# routev11_2.net
KiCad netlist of a schematic drawn in EAGLE
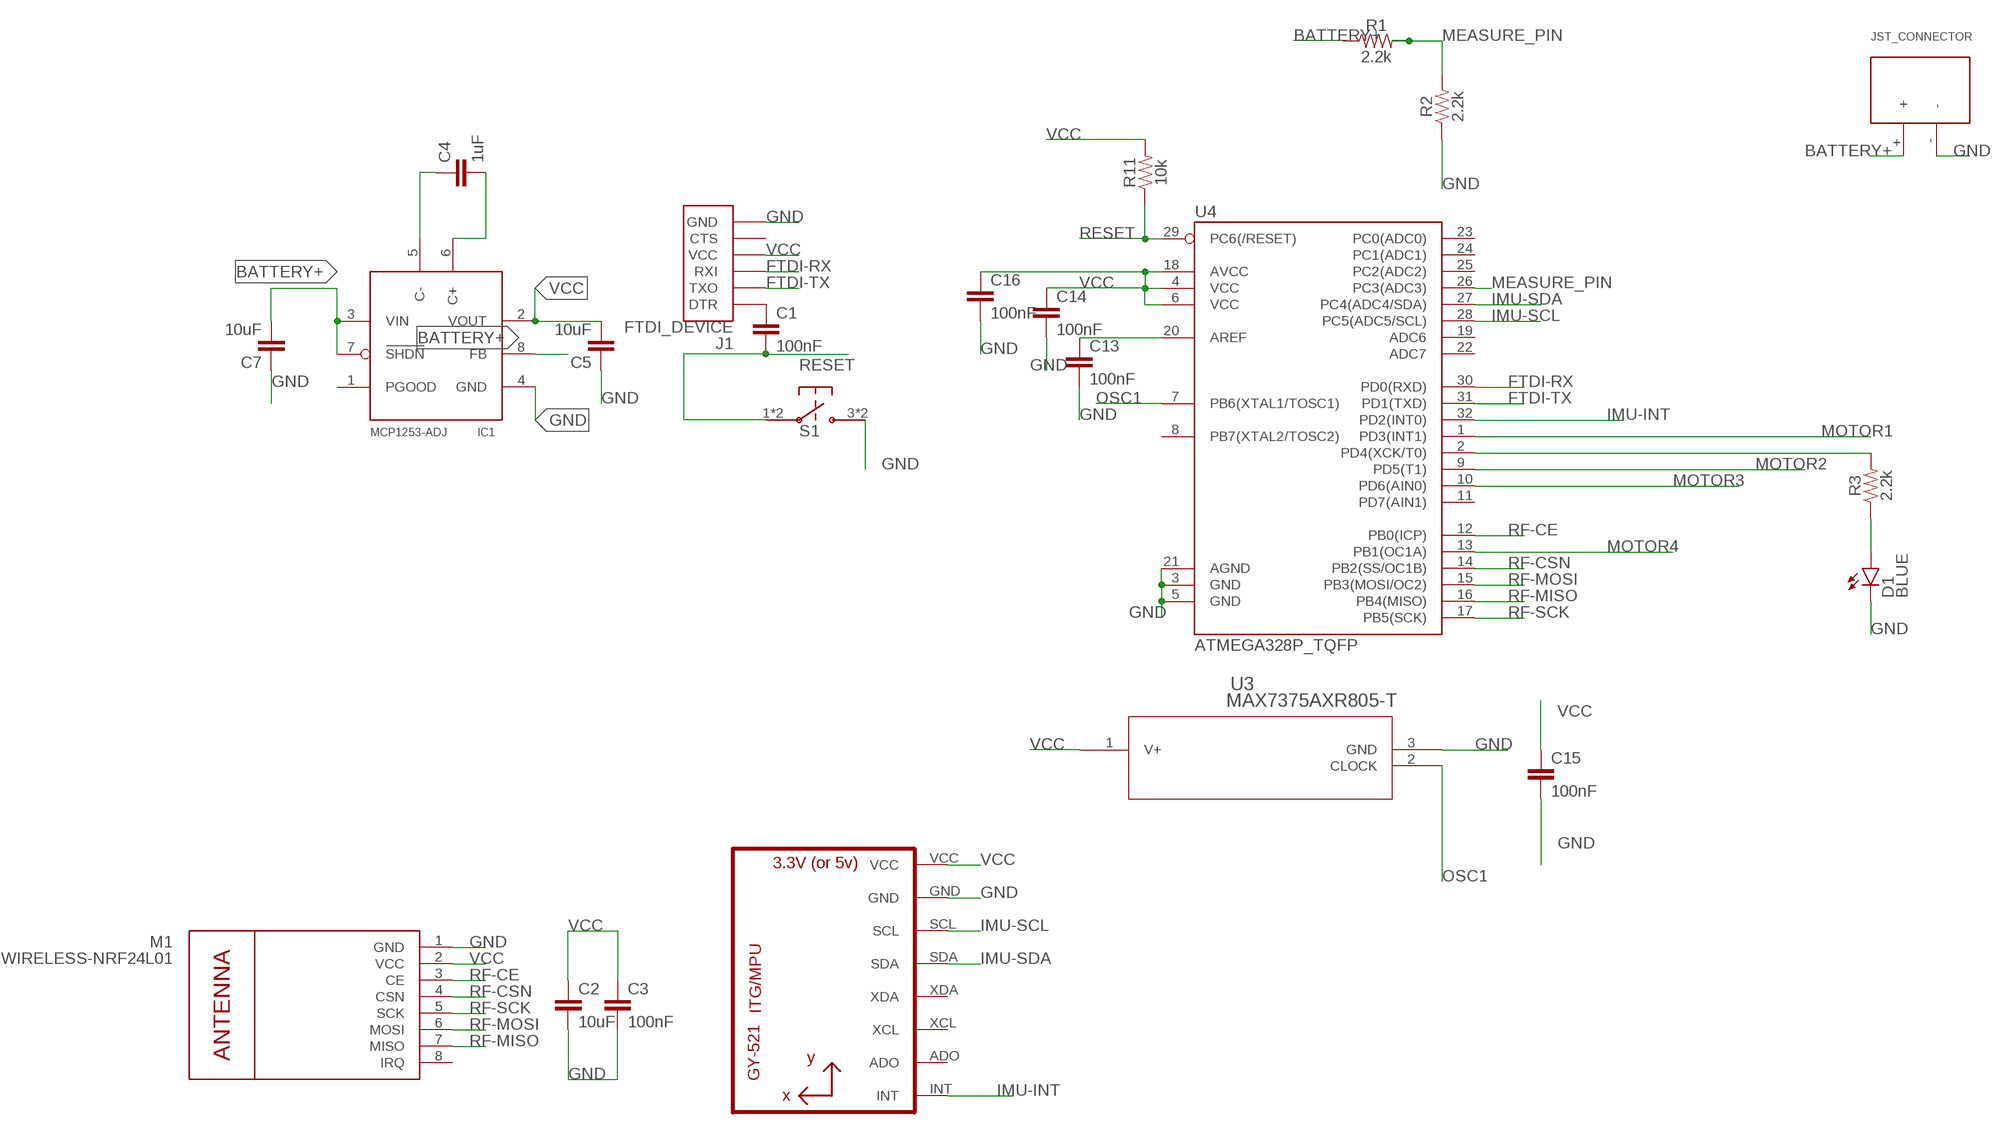
[diagram p0: schematic, sheet 1, part 1 of 2]
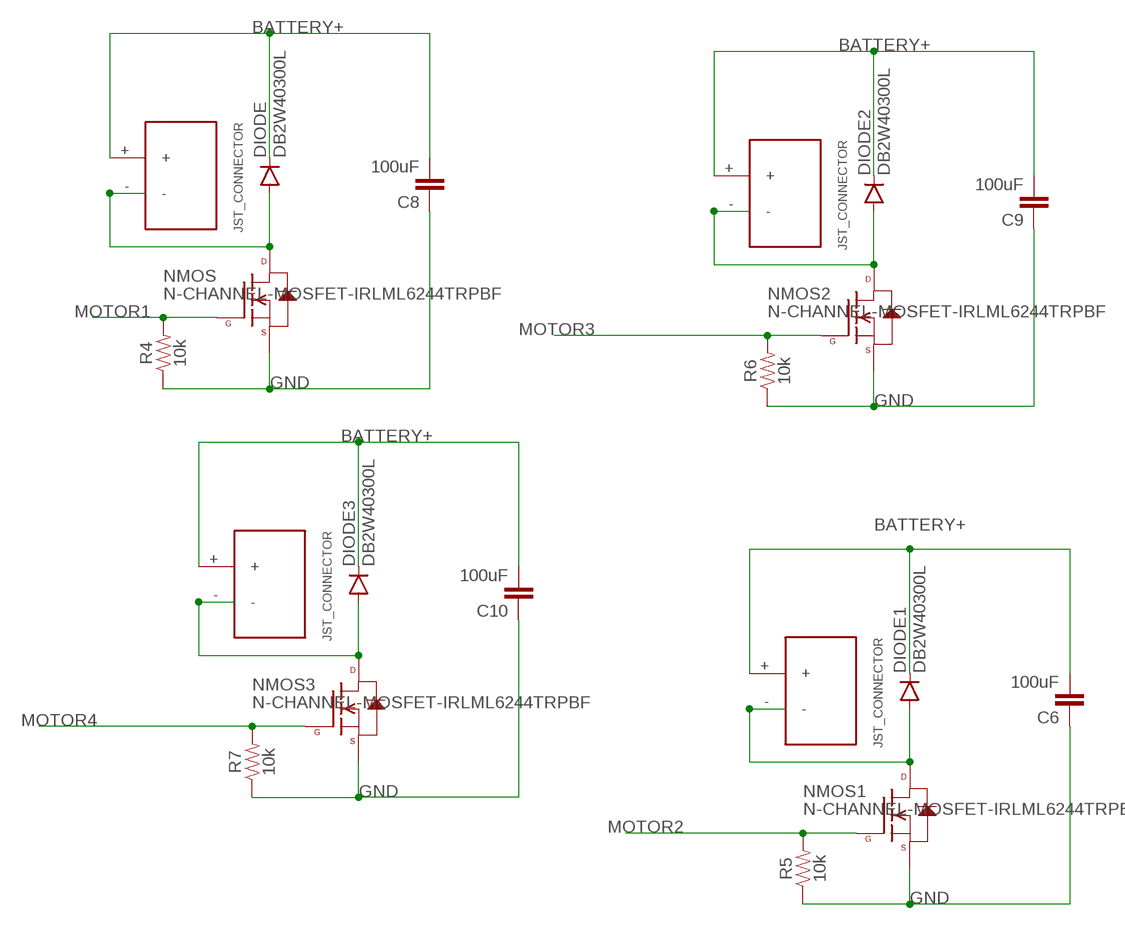
[diagram p1: schematic, sheet 1, part 2 of 2]

(export (version "E")
  (design (tool "Eeschema 10.0.6"))
  (components
    (comp (ref "C1")
      (value "100nF")
      (footprint "eagle-import:0603-CAP")
      (libsource (lib "eagle-import") (part "0.1UF-25V(+80/-20%)(0603)"))
    )
    (comp (ref "C2")
      (value "10uF")
      (footprint "eagle-import:0603-CAP")
      (libsource (lib "eagle-import") (part "CAP0603-CAP"))
    )
    (comp (ref "C3")
      (value "100nF")
      (footprint "eagle-import:0603-CAP")
      (libsource (lib "eagle-import") (part "CAP0603-CAP"))
    )
    (comp (ref "C4")
      (value "1uF")
      (footprint "eagle-import:0603-CAP")
      (libsource (lib "eagle-import") (part "0.1UF-25V(+80/-20%)(0603)"))
    )
    (comp (ref "C5")
      (value "10uF")
      (footprint "eagle-import:0603-CAP")
      (libsource (lib "eagle-import") (part "0.1UF-25V(+80/-20%)(0603)"))
    )
    (comp (ref "C6")
      (value "100uF")
      (footprint "eagle-import:1206")
      (libsource (lib "eagle-import") (part "CAP1206"))
    )
    (comp (ref "C7")
      (value "10uF")
      (footprint "eagle-import:0603-CAP")
      (libsource (lib "eagle-import") (part "0.1UF-25V(+80/-20%)(0603)"))
    )
    (comp (ref "C8")
      (value "100uF")
      (footprint "eagle-import:1206")
      (libsource (lib "eagle-import") (part "CAP1206"))
    )
    (comp (ref "C9")
      (value "100uF")
      (footprint "eagle-import:1206")
      (libsource (lib "eagle-import") (part "CAP1206"))
    )
    (comp (ref "C10")
      (value "100uF")
      (footprint "eagle-import:1206")
      (libsource (lib "eagle-import") (part "CAP1206"))
    )
    (comp (ref "C13")
      (value "100nF")
      (footprint "eagle-import:0603-CAP")
      (libsource (lib "eagle-import") (part "CAP0603-CAP"))
    )
    (comp (ref "C14")
      (value "100nF")
      (footprint "eagle-import:0603-CAP")
      (libsource (lib "eagle-import") (part "CAP0603-CAP"))
    )
    (comp (ref "C15")
      (value "100nF")
      (footprint "eagle-import:0603-CAP")
      (libsource (lib "eagle-import") (part "0.1UF-25V(+80/-20%)(0603)"))
    )
    (comp (ref "C16")
      (value "100nF")
      (footprint "eagle-import:0603-CAP")
      (libsource (lib "eagle-import") (part "CAP0603-CAP"))
    )
    (comp (ref "D1")
      (value "BLUE")
      (footprint "eagle-import:LED-0603")
      (fields (field (name "SPICEPREFIX") "D"))
      (libsource (lib "eagle-import") (part "LED-BLUE0603"))
    )
    (comp (ref "DIODE")
      (value "DB2W40300L")
      (footprint "eagle-import:MINI2-F3-B")
      (libsource (lib "eagle-import") (part "DB2W40300L"))
    )
    (comp (ref "DIODE1")
      (value "DB2W40300L")
      (footprint "eagle-import:MINI2-F3-B")
      (libsource (lib "eagle-import") (part "DB2W40300L"))
    )
    (comp (ref "DIODE2")
      (value "DB2W40300L")
      (footprint "eagle-import:MINI2-F3-B")
      (libsource (lib "eagle-import") (part "DB2W40300L"))
    )
    (comp (ref "DIODE3")
      (value "DB2W40300L")
      (footprint "eagle-import:MINI2-F3-B")
      (libsource (lib "eagle-import") (part "DB2W40300L"))
    )
    (comp (ref "IC1")
      (value "MCP1253-ADJ")
      (footprint "eagle-import:MSOP8")
      (libsource (lib "eagle-import") (part "MCP1253-ADJ"))
    )
    (comp (ref "J1")
      (value "FTDI_DEVICE")
      (footprint "eagle-import:FTDI_DEVICE_SIDE")
      (libsource (lib "eagle-import") (part "FTDI_DEVICE"))
    )
    (comp (ref "M1")
      (value "WIRELESS-NRF24L01")
      (footprint "eagle-import:WIRELESS-NRF24L01")
      (libsource (lib "eagle-import") (part "WIRELESS-NRF24L01"))
    )
    (comp (ref "MOTOR1")
      (value "JST_CONNECTOR_FEMALE")
      (footprint "eagle-import:JST_CONNECTOR_FEMALE")
      (libsource (lib "eagle-import") (part "JST_CONNECTOR_FEMALE"))
    )
    (comp (ref "MOTOR2")
      (value "JST_CONNECTOR_FEMALE")
      (footprint "eagle-import:JST_CONNECTOR_FEMALE")
      (libsource (lib "eagle-import") (part "JST_CONNECTOR_FEMALE"))
    )
    (comp (ref "MOTOR3")
      (value "JST_CONNECTOR_FEMALE")
      (footprint "eagle-import:JST_CONNECTOR_FEMALE")
      (libsource (lib "eagle-import") (part "JST_CONNECTOR_FEMALE"))
    )
    (comp (ref "MOTOR4")
      (value "JST_CONNECTOR_FEMALE")
      (footprint "eagle-import:JST_CONNECTOR_FEMALE")
      (libsource (lib "eagle-import") (part "JST_CONNECTOR_FEMALE"))
    )
    (comp (ref "NMOS")
      (value "N-CHANNEL-MOSFET-IRLML6244TRPBF")
      (footprint "eagle-import:SOT23-3")
      (libsource (lib "eagle-import") (part "N-CHANNEL-MOSFET-IRLML6244TRPBF"))
    )
    (comp (ref "NMOS1")
      (value "N-CHANNEL-MOSFET-IRLML6244TRPBF")
      (footprint "eagle-import:SOT23-3")
      (libsource (lib "eagle-import") (part "N-CHANNEL-MOSFET-IRLML6244TRPBF"))
    )
    (comp (ref "NMOS2")
      (value "N-CHANNEL-MOSFET-IRLML6244TRPBF")
      (footprint "eagle-import:SOT23-3")
      (libsource (lib "eagle-import") (part "N-CHANNEL-MOSFET-IRLML6244TRPBF"))
    )
    (comp (ref "NMOS3")
      (value "N-CHANNEL-MOSFET-IRLML6244TRPBF")
      (footprint "eagle-import:SOT23-3")
      (libsource (lib "eagle-import") (part "N-CHANNEL-MOSFET-IRLML6244TRPBF"))
    )
    (comp (ref "R1")
      (value "2.2k")
      (footprint "eagle-import:0603")
      (libsource (lib "eagle-import") (part "2.2KOHM-0603-1/10W-1%"))
    )
    (comp (ref "R2")
      (value "2.2k")
      (footprint "eagle-import:0603")
      (libsource (lib "eagle-import") (part "2.2KOHM-0603-1/10W-1%"))
    )
    (comp (ref "R3")
      (value "2.2k")
      (footprint "eagle-import:0603")
      (fields (field (name "SPICEPREFIX") "R"))
      (libsource (lib "eagle-import") (part "2.2KOHM-0603-1/10W-1%"))
    )
    (comp (ref "R4")
      (value "10k")
      (footprint "eagle-import:0603")
      (libsource (lib "eagle-import") (part "2.2KOHM-0603-1/10W-1%"))
    )
    (comp (ref "R5")
      (value "10k")
      (footprint "eagle-import:0603")
      (libsource (lib "eagle-import") (part "2.2KOHM-0603-1/10W-1%"))
    )
    (comp (ref "R6")
      (value "10k")
      (footprint "eagle-import:0603")
      (libsource (lib "eagle-import") (part "2.2KOHM-0603-1/10W-1%"))
    )
    (comp (ref "R7")
      (value "10k")
      (footprint "eagle-import:0603")
      (libsource (lib "eagle-import") (part "2.2KOHM-0603-1/10W-1%"))
    )
    (comp (ref "R11")
      (value "10k")
      (footprint "eagle-import:0603")
      (libsource (lib "eagle-import") (part "2.2KOHM-0603-1/10W-1%"))
    )
    (comp (ref "S1")
      (value "TL3315NF100Q")
      (footprint "eagle-import:TL3315NF100Q")
      (fields (field (name "DIGI-KEY_PART_NUMBER") "EG4620CT-ND") (field (name "MF") "E-Switch"))
      (libsource (lib "eagle-import") (part "TL3315NF100Q"))
    )
    (comp (ref "U$1")
      (value "JST_CONNECTOR_FEMALE")
      (footprint "eagle-import:JST_CONNECTOR_FEMALE")
      (libsource (lib "eagle-import") (part "JST_CONNECTOR_FEMALE"))
    )
    (comp (ref "U2")
      (value "GY-521MPU6050")
      (footprint "eagle-import:GY-521")
      (libsource (lib "eagle-import") (part "GY-521MPU6050"))
    )
    (comp (ref "U3")
      (value "MAX7375AXR805-T")
      (footprint "eagle-import:21-0075D")
      (fields (field (name "MF") "Maxim Integrated") (field (name "MP") "MAX7375AXR805+T"))
      (libsource (lib "eagle-import") (part "MAX7375AXR805-T"))
    )
    (comp (ref "U4")
      (value "ATMEGA328P_TQFP")
      (footprint "eagle-import:TQFP32-08")
      (libsource (lib "eagle-import") (part "ATMEGA328P_TQFP"))
    )
  )
  (nets
    (net (code "1") (name "BATTERY+") (class "Default")
      (node (ref "C10") (pin "2") (pinfunction "2_2") (pintype "passive"))
      (node (ref "C6") (pin "2") (pinfunction "2_2") (pintype "passive"))
      (node (ref "C7") (pin "2") (pinfunction "2_2") (pintype "passive"))
      (node (ref "C8") (pin "2") (pinfunction "2_2") (pintype "passive"))
      (node (ref "C9") (pin "2") (pinfunction "2_2") (pintype "passive"))
      (node (ref "DIODE") (pin "NEG") (pinfunction "GPIN_NEG") (pintype "passive"))
      (node (ref "DIODE1") (pin "NEG") (pinfunction "GPIN_NEG") (pintype "passive"))
      (node (ref "DIODE2") (pin "NEG") (pinfunction "GPIN_NEG") (pintype "passive"))
      (node (ref "DIODE3") (pin "NEG") (pinfunction "GPIN_NEG") (pintype "passive"))
      (node (ref "IC1") (pin "3") (pinfunction "VIN_3") (pintype "power_in"))
      (node (ref "IC1") (pin "7") (pinfunction "SHDN_7") (pintype "input"))
      (node (ref "IC1") (pin "8") (pinfunction "FB_8") (pintype "input"))
      (node (ref "MOTOR1") (pin "+") (pinfunction "+_+") (pintype "bidirectional"))
      (node (ref "MOTOR2") (pin "+") (pinfunction "+_+") (pintype "bidirectional"))
      (node (ref "MOTOR3") (pin "+") (pinfunction "+_+") (pintype "bidirectional"))
      (node (ref "MOTOR4") (pin "+") (pinfunction "+_+") (pintype "bidirectional"))
      (node (ref "R1") (pin "1") (pinfunction "1_1") (pintype "passive"))
      (node (ref "U$1") (pin "+") (pinfunction "+_+") (pintype "bidirectional"))
    )
    (net (code "2") (name "FTDI-RX") (class "Default")
      (node (ref "J1") (pin "P$3") (pinfunction "RXI_P$3") (pintype "bidirectional"))
      (node (ref "U4") (pin "30") (pinfunction "PD0(RXD)_30") (pintype "bidirectional"))
    )
    (net (code "3") (name "FTDI-TX") (class "Default")
      (node (ref "J1") (pin "P$2") (pinfunction "TXO_P$2") (pintype "bidirectional"))
      (node (ref "U4") (pin "31") (pinfunction "PD1(TXD)_31") (pintype "bidirectional"))
    )
    (net (code "4") (name "GND") (class "Default")
      (node (ref "C10") (pin "1") (pinfunction "1_1") (pintype "passive"))
      (node (ref "C13") (pin "2") (pinfunction "2_2") (pintype "passive"))
      (node (ref "C14") (pin "2") (pinfunction "2_2") (pintype "passive"))
      (node (ref "C15") (pin "2") (pinfunction "2_2") (pintype "passive"))
      (node (ref "C16") (pin "2") (pinfunction "2_2") (pintype "passive"))
      (node (ref "C2") (pin "2") (pinfunction "2_2") (pintype "passive"))
      (node (ref "C3") (pin "2") (pinfunction "2_2") (pintype "passive"))
      (node (ref "C5") (pin "1") (pinfunction "1_1") (pintype "passive"))
      (node (ref "C6") (pin "1") (pinfunction "1_1") (pintype "passive"))
      (node (ref "C7") (pin "1") (pinfunction "1_1") (pintype "passive"))
      (node (ref "C8") (pin "1") (pinfunction "1_1") (pintype "passive"))
      (node (ref "C9") (pin "1") (pinfunction "1_1") (pintype "passive"))
      (node (ref "D1") (pin "C") (pinfunction "C_C") (pintype "passive"))
      (node (ref "IC1") (pin "4") (pinfunction "GND_4") (pintype "power_in"))
      (node (ref "J1") (pin "P$6") (pinfunction "GND_P$6") (pintype "bidirectional"))
      (node (ref "M1") (pin "1") (pinfunction "GND_1") (pintype "power_in"))
      (node (ref "NMOS") (pin "2") (pinfunction "S_2") (pintype "passive"))
      (node (ref "NMOS1") (pin "2") (pinfunction "S_2") (pintype "passive"))
      (node (ref "NMOS2") (pin "2") (pinfunction "S_2") (pintype "passive"))
      (node (ref "NMOS3") (pin "2") (pinfunction "S_2") (pintype "passive"))
      (node (ref "R2") (pin "1") (pinfunction "1_1") (pintype "passive"))
      (node (ref "R4") (pin "1") (pinfunction "1_1") (pintype "passive"))
      (node (ref "R5") (pin "1") (pinfunction "1_1") (pintype "passive"))
      (node (ref "R6") (pin "1") (pinfunction "1_1") (pintype "passive"))
      (node (ref "R7") (pin "1") (pinfunction "1_1") (pintype "passive"))
      (node (ref "S1") (pin "3") (pinfunction "P$2_3") (pintype "passive"))
      (node (ref "S1") (pin "4") (pinfunction "P$2_4") (pintype "passive"))
      (node (ref "U$1") (pin "-") (pinfunction "-_-") (pintype "bidirectional"))
      (node (ref "U2") (pin "GND") (pinfunction "GND_GND") (pintype "bidirectional"))
      (node (ref "U3") (pin "3") (pinfunction "GND_3") (pintype "power_in"))
      (node (ref "U4") (pin "21") (pinfunction "AGND_21") (pintype "bidirectional"))
      (node (ref "U4") (pin "3") (pinfunction "GND_3") (pintype "bidirectional"))
      (node (ref "U4") (pin "5") (pinfunction "GND_5") (pintype "bidirectional"))
    )
    (net (code "5") (name "IMU-INT") (class "Default")
      (node (ref "U2") (pin "INT") (pinfunction "INT_INT") (pintype "bidirectional"))
      (node (ref "U4") (pin "32") (pinfunction "PD2(INT0)_32") (pintype "bidirectional"))
    )
    (net (code "6") (name "IMU-SCL") (class "Default")
      (node (ref "U2") (pin "SCL") (pinfunction "SCL_SCL") (pintype "bidirectional"))
      (node (ref "U4") (pin "28") (pinfunction "PC5(ADC5/SCL)_28") (pintype "bidirectional"))
    )
    (net (code "7") (name "IMU-SDA") (class "Default")
      (node (ref "U2") (pin "SDA") (pinfunction "SDA_SDA") (pintype "bidirectional"))
      (node (ref "U4") (pin "27") (pinfunction "PC4(ADC4/SDA)_27") (pintype "bidirectional"))
    )
    (net (code "8") (name "MEASURE_PIN") (class "Default")
      (node (ref "R1") (pin "2") (pinfunction "2_2") (pintype "passive"))
      (node (ref "R2") (pin "2") (pinfunction "2_2") (pintype "passive"))
      (node (ref "U4") (pin "26") (pinfunction "PC3(ADC3)_26") (pintype "bidirectional"))
    )
    (net (code "9") (name "MOTOR1") (class "Default")
      (node (ref "NMOS") (pin "1") (pinfunction "G_1") (pintype "passive"))
      (node (ref "R4") (pin "2") (pinfunction "2_2") (pintype "passive"))
      (node (ref "U4") (pin "1") (pinfunction "PD3(INT1)_1") (pintype "bidirectional"))
    )
    (net (code "10") (name "MOTOR2") (class "Default")
      (node (ref "NMOS1") (pin "1") (pinfunction "G_1") (pintype "passive"))
      (node (ref "R5") (pin "2") (pinfunction "2_2") (pintype "passive"))
      (node (ref "U4") (pin "9") (pinfunction "PD5(T1)_9") (pintype "bidirectional"))
    )
    (net (code "11") (name "MOTOR3") (class "Default")
      (node (ref "NMOS2") (pin "1") (pinfunction "G_1") (pintype "passive"))
      (node (ref "R6") (pin "2") (pinfunction "2_2") (pintype "passive"))
      (node (ref "U4") (pin "10") (pinfunction "PD6(AIN0)_10") (pintype "bidirectional"))
    )
    (net (code "12") (name "MOTOR4") (class "Default")
      (node (ref "NMOS3") (pin "1") (pinfunction "G_1") (pintype "passive"))
      (node (ref "R7") (pin "2") (pinfunction "2_2") (pintype "passive"))
      (node (ref "U4") (pin "13") (pinfunction "PB1(OC1A)_13") (pintype "bidirectional"))
    )
    (net (code "13") (name "Net-(D1-PadA)") (class "Default")
      (node (ref "D1") (pin "A") (pinfunction "A_A") (pintype "passive"))
      (node (ref "R3") (pin "1") (pinfunction "1_1") (pintype "passive"))
    )
    (net (code "14") (name "Net-(DIODE-PPIN)") (class "Default")
      (node (ref "DIODE") (pin "POS") (pinfunction "PPIN_POS") (pintype "passive"))
      (node (ref "MOTOR1") (pin "-") (pinfunction "-_-") (pintype "bidirectional"))
      (node (ref "NMOS") (pin "3") (pinfunction "D_3") (pintype "passive"))
    )
    (net (code "15") (name "Net-(DIODE1-PPIN)") (class "Default")
      (node (ref "DIODE1") (pin "POS") (pinfunction "PPIN_POS") (pintype "passive"))
      (node (ref "MOTOR2") (pin "-") (pinfunction "-_-") (pintype "bidirectional"))
      (node (ref "NMOS1") (pin "3") (pinfunction "D_3") (pintype "passive"))
    )
    (net (code "16") (name "Net-(DIODE2-PPIN)") (class "Default")
      (node (ref "DIODE2") (pin "POS") (pinfunction "PPIN_POS") (pintype "passive"))
      (node (ref "MOTOR3") (pin "-") (pinfunction "-_-") (pintype "bidirectional"))
      (node (ref "NMOS2") (pin "3") (pinfunction "D_3") (pintype "passive"))
    )
    (net (code "17") (name "Net-(DIODE3-PPIN)") (class "Default")
      (node (ref "DIODE3") (pin "POS") (pinfunction "PPIN_POS") (pintype "passive"))
      (node (ref "MOTOR4") (pin "-") (pinfunction "-_-") (pintype "bidirectional"))
      (node (ref "NMOS3") (pin "3") (pinfunction "D_3") (pintype "passive"))
    )
    (net (code "18") (name "Net-(IC1-C+)") (class "Default")
      (node (ref "C4") (pin "2") (pinfunction "2_2") (pintype "passive"))
      (node (ref "IC1") (pin "6") (pinfunction "C+_6") (pintype "passive"))
    )
    (net (code "19") (name "Net-(IC1-C-)") (class "Default")
      (node (ref "C4") (pin "1") (pinfunction "1_1") (pintype "passive"))
      (node (ref "IC1") (pin "5") (pinfunction "C-_5") (pintype "passive"))
    )
    (net (code "20") (name "Net-(J1-DTR)") (class "Default")
      (node (ref "C1") (pin "1") (pinfunction "1_1") (pintype "passive"))
      (node (ref "J1") (pin "P$1") (pinfunction "DTR_P$1") (pintype "bidirectional"))
    )
    (net (code "21") (name "Net-(U4-AREF)") (class "Default")
      (node (ref "C13") (pin "1") (pinfunction "1_1") (pintype "passive"))
      (node (ref "U4") (pin "20") (pinfunction "AREF_20") (pintype "bidirectional"))
    )
    (net (code "22") (name "Net-(U4-PD4(XCK{slash}T0))") (class "Default")
      (node (ref "R3") (pin "2") (pinfunction "2_2") (pintype "passive"))
      (node (ref "U4") (pin "2") (pinfunction "PD4(XCK/T0)_2") (pintype "bidirectional"))
    )
    (net (code "23") (name "OSC1") (class "Default")
      (node (ref "U3") (pin "2") (pinfunction "CLOCK_2") (pintype "output"))
      (node (ref "U4") (pin "7") (pinfunction "PB6(XTAL1/TOSC1)_7") (pintype "bidirectional"))
    )
    (net (code "24") (name "RESET") (class "Default")
      (node (ref "C1") (pin "2") (pinfunction "2_2") (pintype "passive"))
      (node (ref "R11") (pin "1") (pinfunction "1_1") (pintype "passive"))
      (node (ref "S1") (pin "1") (pinfunction "P$1_1") (pintype "passive"))
      (node (ref "S1") (pin "2") (pinfunction "P$1_2") (pintype "passive"))
      (node (ref "U4") (pin "29") (pinfunction "PC6(/RESET)_29") (pintype "bidirectional"))
    )
    (net (code "25") (name "RF-CE") (class "Default")
      (node (ref "M1") (pin "3") (pinfunction "CE_3") (pintype "bidirectional"))
      (node (ref "U4") (pin "12") (pinfunction "PB0(ICP)_12") (pintype "bidirectional"))
    )
    (net (code "26") (name "RF-CSN") (class "Default")
      (node (ref "M1") (pin "4") (pinfunction "CSN_4") (pintype "bidirectional"))
      (node (ref "U4") (pin "14") (pinfunction "PB2(SS/OC1B)_14") (pintype "bidirectional"))
    )
    (net (code "27") (name "RF-MISO") (class "Default")
      (node (ref "M1") (pin "7") (pinfunction "MISO_7") (pintype "bidirectional"))
      (node (ref "U4") (pin "16") (pinfunction "PB4(MISO)_16") (pintype "bidirectional"))
    )
    (net (code "28") (name "RF-MOSI") (class "Default")
      (node (ref "M1") (pin "6") (pinfunction "MOSI_6") (pintype "bidirectional"))
      (node (ref "U4") (pin "15") (pinfunction "PB3(MOSI/OC2)_15") (pintype "bidirectional"))
    )
    (net (code "29") (name "RF-SCK") (class "Default")
      (node (ref "M1") (pin "5") (pinfunction "SCK_5") (pintype "bidirectional"))
      (node (ref "U4") (pin "17") (pinfunction "PB5(SCK)_17") (pintype "bidirectional"))
    )
    (net (code "30") (name "VCC") (class "Default")
      (node (ref "C14") (pin "1") (pinfunction "1_1") (pintype "passive"))
      (node (ref "C15") (pin "1") (pinfunction "1_1") (pintype "passive"))
      (node (ref "C16") (pin "1") (pinfunction "1_1") (pintype "passive"))
      (node (ref "C2") (pin "1") (pinfunction "1_1") (pintype "passive"))
      (node (ref "C3") (pin "1") (pinfunction "1_1") (pintype "passive"))
      (node (ref "C5") (pin "2") (pinfunction "2_2") (pintype "passive"))
      (node (ref "IC1") (pin "2") (pinfunction "VOUT_2") (pintype "output"))
      (node (ref "J1") (pin "P$4") (pinfunction "VCC_P$4") (pintype "bidirectional"))
      (node (ref "M1") (pin "2") (pinfunction "VCC_2") (pintype "power_in"))
      (node (ref "R11") (pin "2") (pinfunction "2_2") (pintype "passive"))
      (node (ref "U2") (pin "VCC") (pinfunction "VCC_VCC") (pintype "bidirectional"))
      (node (ref "U3") (pin "1") (pinfunction "V+_1") (pintype "power_in"))
      (node (ref "U4") (pin "18") (pinfunction "AVCC_18") (pintype "bidirectional"))
      (node (ref "U4") (pin "4") (pinfunction "VCC_4") (pintype "bidirectional"))
      (node (ref "U4") (pin "6") (pinfunction "VCC_6") (pintype "bidirectional"))
    )
    (net (code "31") (name "unconnected-(IC1-PGOOD-Pad1)") (class "Default")
      (node (ref "IC1") (pin "1") (pinfunction "PGOOD_1") (pintype "output"))
    )
    (net (code "32") (name "unconnected-(J1-CTS-PadP$5)") (class "Default")
      (node (ref "J1") (pin "P$5") (pinfunction "CTS_P$5") (pintype "bidirectional"))
    )
    (net (code "33") (name "unconnected-(M1-IRQ-Pad8)") (class "Default")
      (node (ref "M1") (pin "8") (pinfunction "IRQ_8") (pintype "bidirectional"))
    )
    (net (code "34") (name "unconnected-(U2-PadADO)") (class "Default")
      (node (ref "U2") (pin "ADO") (pinfunction "ADO_ADO") (pintype "bidirectional"))
    )
    (net (code "35") (name "unconnected-(U2-PadXCL)") (class "Default")
      (node (ref "U2") (pin "XCL") (pinfunction "XCL_XCL") (pintype "bidirectional"))
    )
    (net (code "36") (name "unconnected-(U2-PadXDA)") (class "Default")
      (node (ref "U2") (pin "XDA") (pinfunction "XDA_XDA") (pintype "bidirectional"))
    )
    (net (code "37") (name "unconnected-(U4-ADC6-Pad19)") (class "Default")
      (node (ref "U4") (pin "19") (pinfunction "ADC6_19") (pintype "bidirectional"))
    )
    (net (code "38") (name "unconnected-(U4-ADC7-Pad22)") (class "Default")
      (node (ref "U4") (pin "22") (pinfunction "ADC7_22") (pintype "bidirectional"))
    )
    (net (code "39") (name "unconnected-(U4-PB7(XTAL2{slash}TOSC2)-Pad8)") (class "Default")
      (node (ref "U4") (pin "8") (pinfunction "PB7(XTAL2/TOSC2)_8") (pintype "bidirectional"))
    )
    (net (code "40") (name "unconnected-(U4-PC0(ADC0)-Pad23)") (class "Default")
      (node (ref "U4") (pin "23") (pinfunction "PC0(ADC0)_23") (pintype "bidirectional"))
    )
    (net (code "41") (name "unconnected-(U4-PC1(ADC1)-Pad24)") (class "Default")
      (node (ref "U4") (pin "24") (pinfunction "PC1(ADC1)_24") (pintype "bidirectional"))
    )
    (net (code "42") (name "unconnected-(U4-PC2(ADC2)-Pad25)") (class "Default")
      (node (ref "U4") (pin "25") (pinfunction "PC2(ADC2)_25") (pintype "bidirectional"))
    )
    (net (code "43") (name "unconnected-(U4-PD7(AIN1)-Pad11)") (class "Default")
      (node (ref "U4") (pin "11") (pinfunction "PD7(AIN1)_11") (pintype "bidirectional"))
    )
  )
)
